# SCH_placa_Rorgerio_IGBT_2026-07-28.net
KiCad netlist of a schematic drawn in EasyEDA
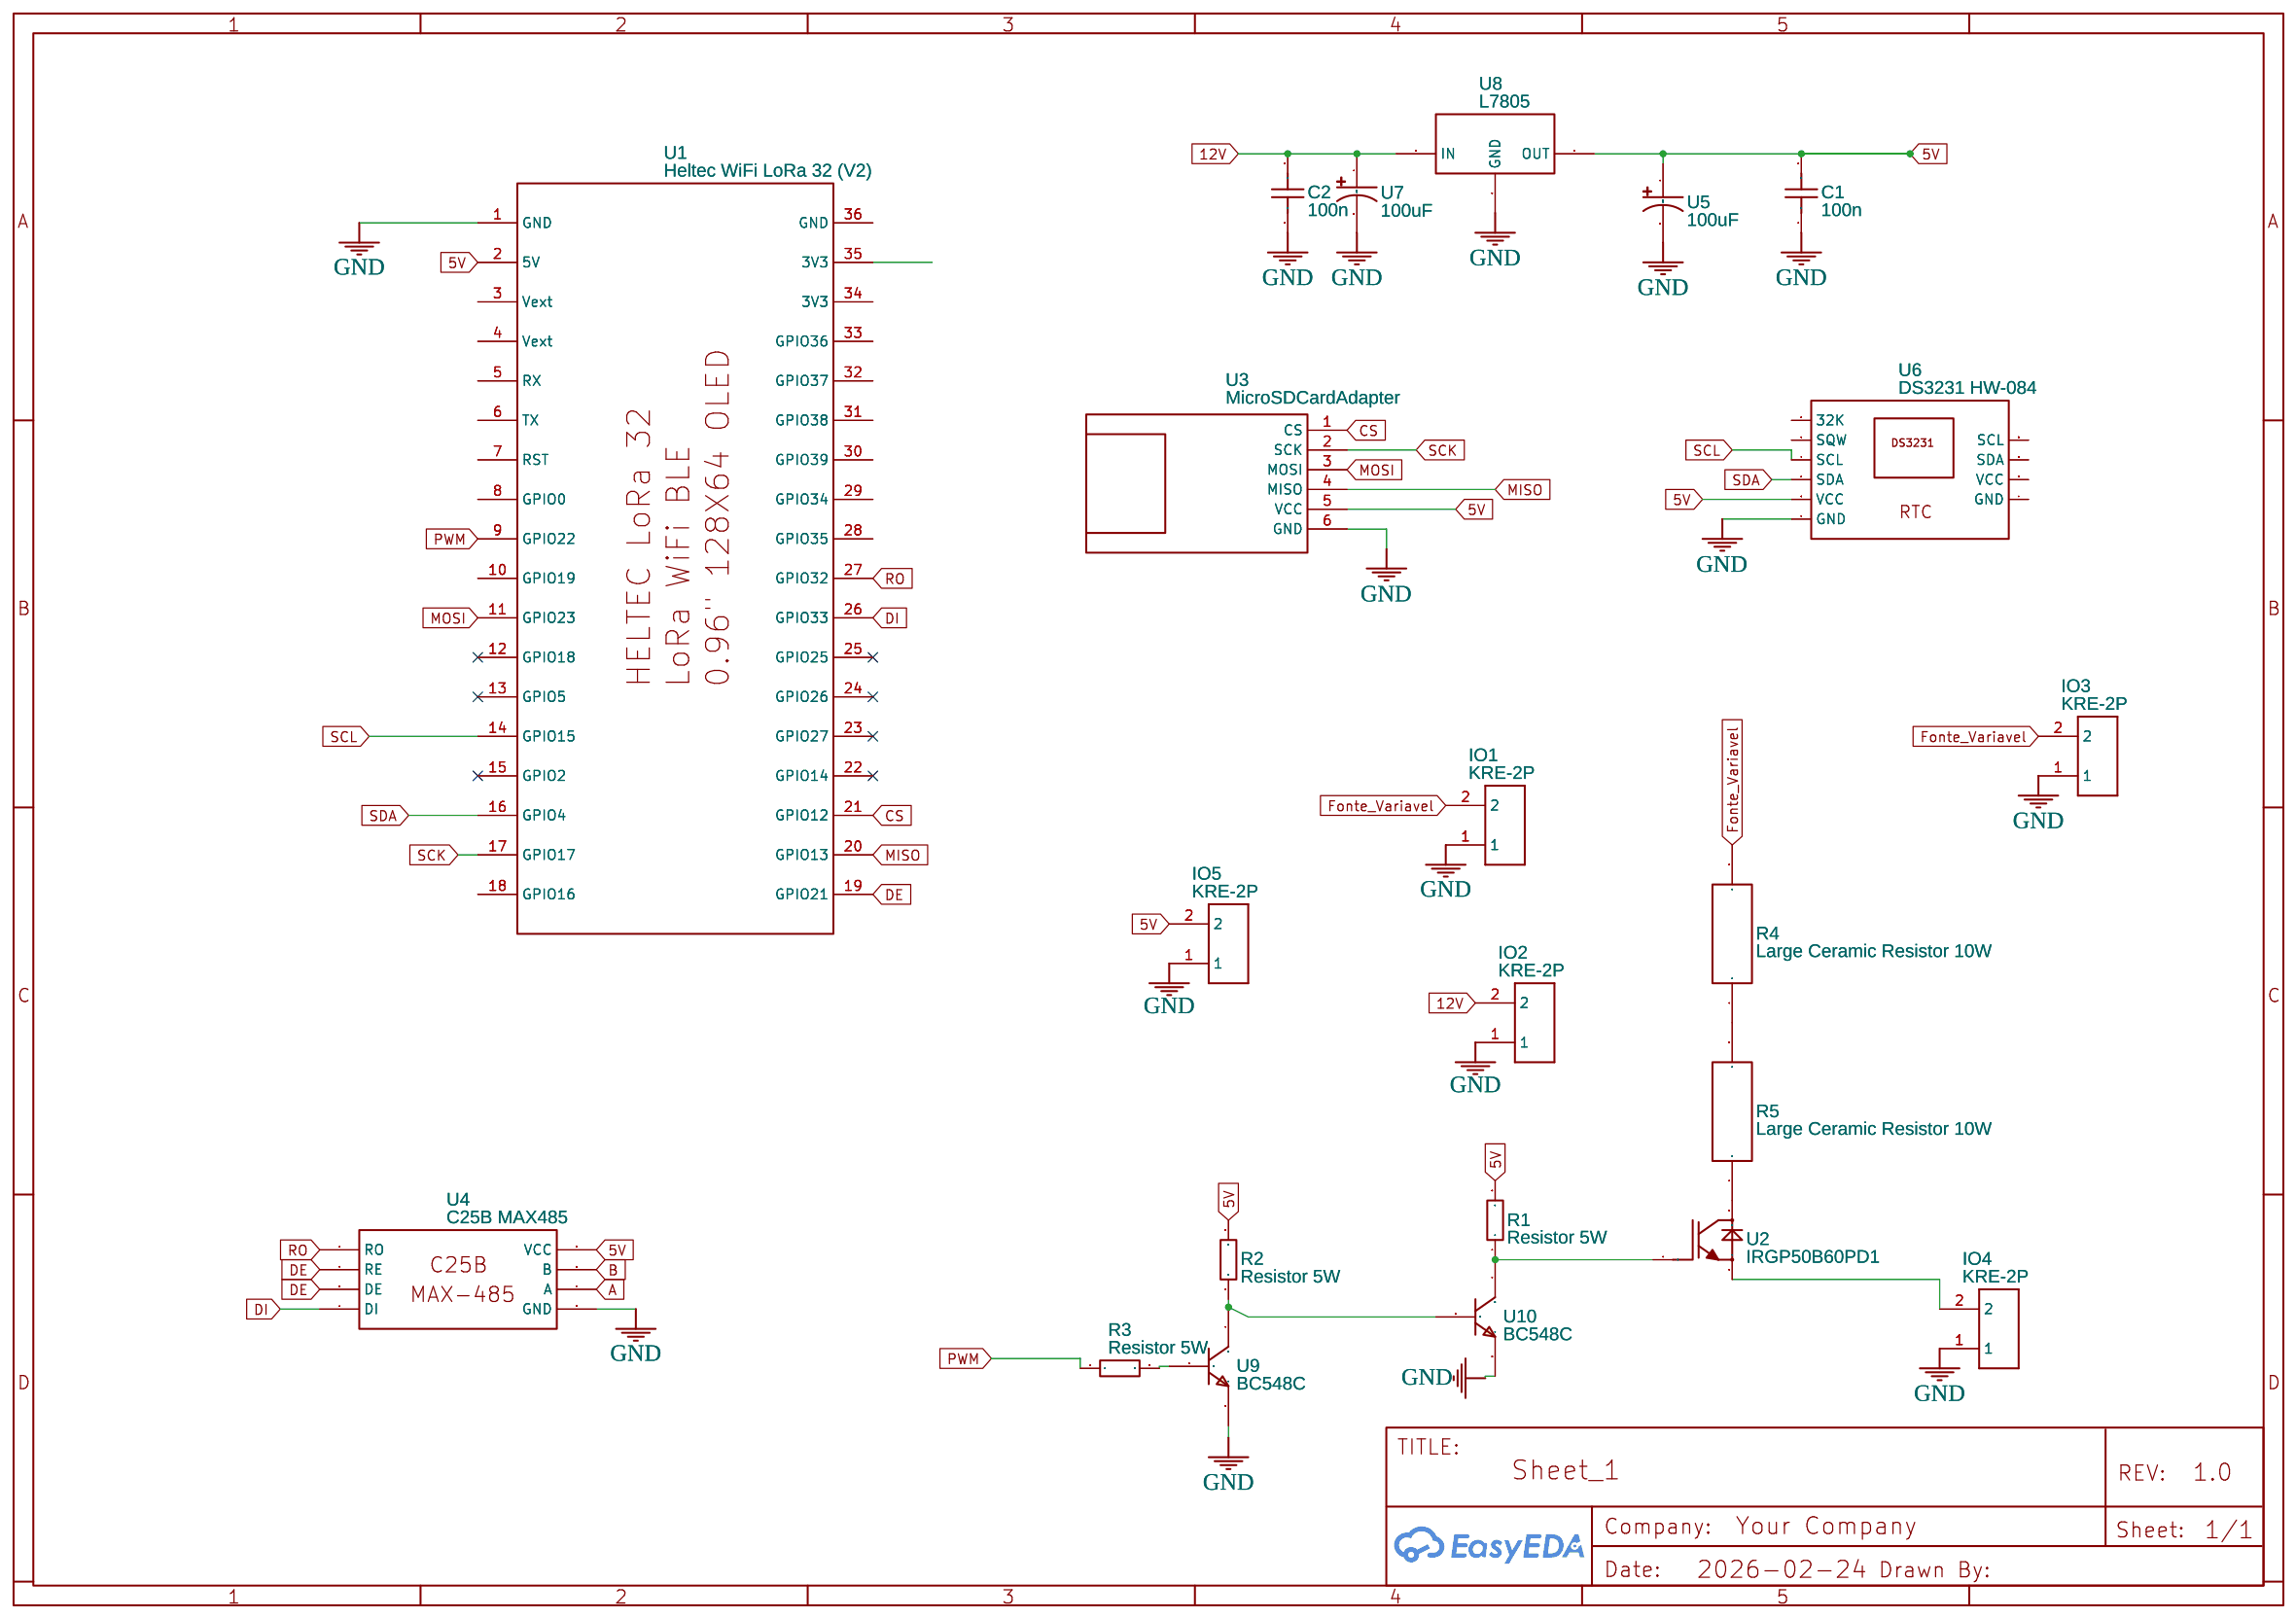
[diagram p0: schematic sheet]

(export (version "E")
  (design (tool "Eeschema 10.0.6"))
  (components
    (comp (ref "C1") (value "100n") (libsource (lib "") (part "C_0603_US")))
    (comp (ref "C2") (value "100n") (libsource (lib "") (part "C_0603_US")))
    (comp (ref "IO1") (value "KRE-2P") (libsource (lib "") (part "KRE-2P")))
    (comp (ref "IO2") (value "KRE-2P") (libsource (lib "") (part "KRE-2P")))
    (comp (ref "IO3") (value "KRE-2P") (libsource (lib "") (part "KRE-2P")))
    (comp (ref "IO4") (value "KRE-2P") (libsource (lib "") (part "KRE-2P")))
    (comp (ref "IO5") (value "KRE-2P") (libsource (lib "") (part "KRE-2P")))
    (comp (ref "R1")
      (value "Resistor 5W")
      (fields (field (name "Manufacturer") "UniOhm"))
      (libsource (lib "") (part "Resistor 5W"))
    )
    (comp (ref "R2")
      (value "Resistor 5W")
      (fields (field (name "Manufacturer") "UniOhm"))
      (libsource (lib "") (part "Resistor 5W"))
    )
    (comp (ref "R3")
      (value "Resistor 5W")
      (fields (field (name "Manufacturer") "UniOhm"))
      (libsource (lib "") (part "Resistor 5W_1"))
    )
    (comp (ref "R4")
      (value "Large Ceramic Resistor 10W")
      (fields (field (name "Manufacturer Part") "Yontex MKP 250V 6.8uF"))
      (libsource (lib "") (part "Large Ceramic Resistor 10W"))
    )
    (comp (ref "R5")
      (value "Large Ceramic Resistor 10W")
      (fields (field (name "Manufacturer Part") "Yontex MKP 250V 6.8uF"))
      (libsource (lib "") (part "Large Ceramic Resistor 10W"))
    )
    (comp (ref "U1")
      (value "Heltec WiFi LoRa 32 (V2)")
      (fields
        (field (name "Manufacturer Part") "Heltec WiFi LoRa 32(V2)")
        (field (name "Manufacturer") "Heltec")
      )
      (libsource (lib "") (part "Heltec WiFi LoRa 32 (V2)"))
    )
    (comp (ref "U2") (value "IRGP50B60PD1") (libsource (lib "") (part "IRGP50B60PD1")))
    (comp (ref "U3") (value "MicroSDCardAdapter") (libsource (lib "") (part "MicroSDCardAdapter")))
    (comp (ref "U4") (value "C25B MAX485") (libsource (lib "") (part "C25B MAX485")))
    (comp (ref "U5")
      (value "100uF")
      (fields
        (field (name "Manufacturer Part") "EKY-101ETD101MK16S")
        (field (name "Manufacturer") "NCC(日本贵弥功)")
      )
      (libsource (lib "") (part "Cap100uF25V"))
    )
    (comp (ref "U6") (value "DS3231 HW-084") (libsource (lib "") (part "DS3231 HW-084")))
    (comp (ref "U7")
      (value "100uF")
      (fields
        (field (name "Manufacturer Part") "EKY-101ETD101MK16S")
        (field (name "Manufacturer") "NCC(日本贵弥功)")
      )
      (libsource (lib "") (part "Cap100uF25V"))
    )
    (comp (ref "U8") (value "L7805") (libsource (lib "") (part "L7805")))
    (comp (ref "U9") (value "BC548C") (libsource (lib "") (part "BC548C")))
    (comp (ref "U10") (value "BC548C") (libsource (lib "") (part "BC548C")))
  )
  (nets
    (net (code "1") (name "5V") (class "Default")
      (node (ref "C1") (pin "2") (pinfunction "2_2") (pintype "unspecified"))
      (node (ref "IO5") (pin "2") (pinfunction "2_2") (pintype "unspecified"))
      (node (ref "R1") (pin "2") (pinfunction "2_2") (pintype "input"))
      (node (ref "R2") (pin "2") (pinfunction "2_2") (pintype "input"))
      (node (ref "U1") (pin "2") (pinfunction "5V_2") (pintype "unspecified"))
      (node (ref "U3") (pin "5") (pinfunction "VCC_5") (pintype "unspecified"))
      (node (ref "U4") (pin "5") (pinfunction "VCC_5") (pintype "unspecified"))
      (node (ref "U5") (pin "1") (pinfunction "1_1") (pintype "unspecified"))
      (node (ref "U6") (pin "2") (pinfunction "VCC_2") (pintype "passive"))
      (node (ref "U8") (pin "1") (pinfunction "OUT_1") (pintype "unspecified"))
    )
    (net (code "2") (name "12V") (class "Default")
      (node (ref "C2") (pin "2") (pinfunction "2_2") (pintype "unspecified"))
      (node (ref "IO2") (pin "2") (pinfunction "2_2") (pintype "unspecified"))
      (node (ref "U7") (pin "1") (pinfunction "1_1") (pintype "unspecified"))
      (node (ref "U8") (pin "3") (pinfunction "IN_3") (pintype "unspecified"))
    )
    (net (code "3") (name "A") (class "Default")
      (node (ref "U4") (pin "7") (pinfunction "A_7") (pintype "unspecified"))
    )
    (net (code "4") (name "B") (class "Default")
      (node (ref "U4") (pin "6") (pinfunction "B_6") (pintype "unspecified"))
    )
    (net (code "5") (name "CS") (class "Default")
      (node (ref "U1") (pin "21") (pinfunction "GPIO12_21") (pintype "unspecified"))
      (node (ref "U3") (pin "1") (pinfunction "CS_1") (pintype "unspecified"))
    )
    (net (code "6") (name "DE") (class "Default")
      (node (ref "U1") (pin "19") (pinfunction "GPIO21_19") (pintype "unspecified"))
      (node (ref "U4") (pin "2") (pinfunction "RE_2") (pintype "unspecified"))
      (node (ref "U4") (pin "3") (pinfunction "DE_3") (pintype "unspecified"))
    )
    (net (code "7") (name "DI") (class "Default")
      (node (ref "U1") (pin "26") (pinfunction "GPIO33_26") (pintype "unspecified"))
      (node (ref "U4") (pin "4") (pinfunction "DI_4") (pintype "unspecified"))
    )
    (net (code "8") (name "Fonte_Variavel") (class "Default")
      (node (ref "IO1") (pin "2") (pinfunction "2_2") (pintype "unspecified"))
      (node (ref "IO3") (pin "2") (pinfunction "2_2") (pintype "unspecified"))
      (node (ref "R4") (pin "2") (pinfunction "2_2") (pintype "unspecified"))
    )
    (net (code "9") (name "GND") (class "Default")
      (node (ref "C1") (pin "1") (pinfunction "1_1") (pintype "unspecified"))
      (node (ref "C2") (pin "1") (pinfunction "1_1") (pintype "unspecified"))
      (node (ref "IO1") (pin "1") (pinfunction "1_1") (pintype "unspecified"))
      (node (ref "IO2") (pin "1") (pinfunction "1_1") (pintype "unspecified"))
      (node (ref "IO3") (pin "1") (pinfunction "1_1") (pintype "unspecified"))
      (node (ref "IO4") (pin "1") (pinfunction "1_1") (pintype "unspecified"))
      (node (ref "IO5") (pin "1") (pinfunction "1_1") (pintype "unspecified"))
      (node (ref "U1") (pin "1") (pinfunction "GND_1") (pintype "unspecified"))
      (node (ref "U10") (pin "3") (pinfunction "E_3") (pintype "unspecified"))
      (node (ref "U3") (pin "6") (pinfunction "GND_6") (pintype "unspecified"))
      (node (ref "U4") (pin "8") (pinfunction "GND_8") (pintype "unspecified"))
      (node (ref "U5") (pin "2") (pinfunction "2_2") (pintype "unspecified"))
      (node (ref "U6") (pin "1") (pinfunction "GND_1") (pintype "passive"))
      (node (ref "U7") (pin "2") (pinfunction "2_2") (pintype "unspecified"))
      (node (ref "U8") (pin "2") (pinfunction "GND_2") (pintype "unspecified"))
      (node (ref "U9") (pin "3") (pinfunction "E_3") (pintype "unspecified"))
    )
    (net (code "10") (name "MISO") (class "Default")
      (node (ref "U1") (pin "20") (pinfunction "GPIO13_20") (pintype "unspecified"))
      (node (ref "U3") (pin "4") (pinfunction "MISO_4") (pintype "unspecified"))
    )
    (net (code "11") (name "MOSI") (class "Default")
      (node (ref "U1") (pin "11") (pinfunction "GPIO23_11") (pintype "unspecified"))
      (node (ref "U3") (pin "3") (pinfunction "MOSI_3") (pintype "unspecified"))
    )
    (net (code "12") (name "Net-(R4-Pad1)") (class "Default")
      (node (ref "R4") (pin "1") (pinfunction "1_1") (pintype "unspecified"))
      (node (ref "R5") (pin "2") (pinfunction "2_2") (pintype "unspecified"))
    )
    (net (code "13") (name "Net-(U2-C)") (class "Default")
      (node (ref "R5") (pin "1") (pinfunction "1_1") (pintype "unspecified"))
      (node (ref "U2") (pin "2") (pinfunction "C_2") (pintype "unspecified"))
    )
    (net (code "14") (name "Net-(U2-E)") (class "Default")
      (node (ref "IO4") (pin "2") (pinfunction "2_2") (pintype "unspecified"))
      (node (ref "U2") (pin "3") (pinfunction "E_3") (pintype "unspecified"))
    )
    (net (code "15") (name "Net-(U9-B)") (class "Default")
      (node (ref "R3") (pin "2") (pinfunction "2_2") (pintype "input"))
      (node (ref "U9") (pin "2") (pinfunction "B_2") (pintype "unspecified"))
    )
    (net (code "16") (name "Net-(U10-B)") (class "Default")
      (node (ref "R2") (pin "1") (pinfunction "1_1") (pintype "input"))
      (node (ref "U10") (pin "2") (pinfunction "B_2") (pintype "unspecified"))
      (node (ref "U9") (pin "1") (pinfunction "C_1") (pintype "unspecified"))
    )
    (net (code "17") (name "Net-(U10-C)") (class "Default")
      (node (ref "R1") (pin "1") (pinfunction "1_1") (pintype "input"))
      (node (ref "U10") (pin "1") (pinfunction "C_1") (pintype "unspecified"))
      (node (ref "U2") (pin "1") (pinfunction "G_1") (pintype "unspecified"))
    )
    (net (code "18") (name "PWM") (class "Default")
      (node (ref "R3") (pin "1") (pinfunction "1_1") (pintype "input"))
      (node (ref "U1") (pin "9") (pinfunction "GPIO22_9") (pintype "unspecified"))
    )
    (net (code "19") (name "RO") (class "Default")
      (node (ref "U1") (pin "27") (pinfunction "GPIO32_27") (pintype "unspecified"))
      (node (ref "U4") (pin "1") (pinfunction "RO_1") (pintype "unspecified"))
    )
    (net (code "20") (name "SCK") (class "Default")
      (node (ref "U1") (pin "17") (pinfunction "GPIO17_17") (pintype "unspecified"))
      (node (ref "U3") (pin "2") (pinfunction "SCK_2") (pintype "unspecified"))
    )
    (net (code "21") (name "SCL") (class "Default")
      (node (ref "U1") (pin "14") (pinfunction "GPIO15_14") (pintype "unspecified"))
      (node (ref "U6") (pin "4") (pinfunction "SCL_4") (pintype "unspecified"))
    )
    (net (code "22") (name "SDA") (class "Default")
      (node (ref "U1") (pin "16") (pinfunction "GPIO4_16") (pintype "unspecified"))
      (node (ref "U6") (pin "3") (pinfunction "SDA_3") (pintype "bidirectional"))
    )
    (net (code "23") (name "unconnected-(U1-3V3-Pad34)") (class "Default")
      (node (ref "U1") (pin "34") (pinfunction "3V3_34") (pintype "unspecified"))
    )
    (net (code "24") (name "unconnected-(U1-3V3-Pad35)") (class "Default")
      (node (ref "U1") (pin "35") (pinfunction "3V3_35") (pintype "unspecified"))
    )
    (net (code "25") (name "unconnected-(U1-GND-Pad36)") (class "Default")
      (node (ref "U1") (pin "36") (pinfunction "GND_36") (pintype "unspecified"))
    )
    (net (code "26") (name "unconnected-(U1-GPIO0-Pad8)") (class "Default")
      (node (ref "U1") (pin "8") (pinfunction "GPIO0_8") (pintype "unspecified"))
    )
    (net (code "27") (name "unconnected-(U1-GPIO2-Pad15)") (class "Default")
      (node (ref "U1") (pin "15") (pinfunction "GPIO2_15") (pintype "unspecified+no_connect"))
    )
    (net (code "28") (name "unconnected-(U1-GPIO5-Pad13)") (class "Default")
      (node (ref "U1") (pin "13") (pinfunction "GPIO5_13") (pintype "unspecified+no_connect"))
    )
    (net (code "29") (name "unconnected-(U1-GPIO14-Pad22)") (class "Default")
      (node (ref "U1") (pin "22") (pinfunction "GPIO14_22") (pintype "unspecified+no_connect"))
    )
    (net (code "30") (name "unconnected-(U1-GPIO16-Pad18)") (class "Default")
      (node (ref "U1") (pin "18") (pinfunction "GPIO16_18") (pintype "unspecified"))
    )
    (net (code "31") (name "unconnected-(U1-GPIO18-Pad12)") (class "Default")
      (node (ref "U1") (pin "12") (pinfunction "GPIO18_12") (pintype "unspecified+no_connect"))
    )
    (net (code "32") (name "unconnected-(U1-GPIO19-Pad10)") (class "Default")
      (node (ref "U1") (pin "10") (pinfunction "GPIO19_10") (pintype "unspecified"))
    )
    (net (code "33") (name "unconnected-(U1-GPIO25-Pad25)") (class "Default")
      (node (ref "U1") (pin "25") (pinfunction "GPIO25_25") (pintype "unspecified+no_connect"))
    )
    (net (code "34") (name "unconnected-(U1-GPIO26-Pad24)") (class "Default")
      (node (ref "U1") (pin "24") (pinfunction "GPIO26_24") (pintype "unspecified+no_connect"))
    )
    (net (code "35") (name "unconnected-(U1-GPIO27-Pad23)") (class "Default")
      (node (ref "U1") (pin "23") (pinfunction "GPIO27_23") (pintype "unspecified+no_connect"))
    )
    (net (code "36") (name "unconnected-(U1-GPIO34-Pad29)") (class "Default")
      (node (ref "U1") (pin "29") (pinfunction "GPIO34_29") (pintype "unspecified"))
    )
    (net (code "37") (name "unconnected-(U1-GPIO35-Pad28)") (class "Default")
      (node (ref "U1") (pin "28") (pinfunction "GPIO35_28") (pintype "unspecified"))
    )
    (net (code "38") (name "unconnected-(U1-GPIO36-Pad33)") (class "Default")
      (node (ref "U1") (pin "33") (pinfunction "GPIO36_33") (pintype "unspecified"))
    )
    (net (code "39") (name "unconnected-(U1-GPIO37-Pad32)") (class "Default")
      (node (ref "U1") (pin "32") (pinfunction "GPIO37_32") (pintype "unspecified"))
    )
    (net (code "40") (name "unconnected-(U1-GPIO38-Pad31)") (class "Default")
      (node (ref "U1") (pin "31") (pinfunction "GPIO38_31") (pintype "unspecified"))
    )
    (net (code "41") (name "unconnected-(U1-GPIO39-Pad30)") (class "Default")
      (node (ref "U1") (pin "30") (pinfunction "GPIO39_30") (pintype "unspecified"))
    )
    (net (code "42") (name "unconnected-(U1-RST-Pad7)") (class "Default")
      (node (ref "U1") (pin "7") (pinfunction "RST_7") (pintype "unspecified"))
    )
    (net (code "43") (name "unconnected-(U1-RX-Pad5)") (class "Default")
      (node (ref "U1") (pin "5") (pinfunction "RX_5") (pintype "unspecified"))
    )
    (net (code "44") (name "unconnected-(U1-TX-Pad6)") (class "Default")
      (node (ref "U1") (pin "6") (pinfunction "TX_6") (pintype "unspecified"))
    )
    (net (code "45") (name "unconnected-(U1-Vext-Pad3)") (class "Default")
      (node (ref "U1") (pin "3") (pinfunction "Vext_3") (pintype "unspecified"))
    )
    (net (code "46") (name "unconnected-(U1-Vext-Pad4)") (class "Default")
      (node (ref "U1") (pin "4") (pinfunction "Vext_4") (pintype "unspecified"))
    )
    (net (code "47") (name "unconnected-(U6-32K-Pad6)") (class "Default")
      (node (ref "U6") (pin "6") (pinfunction "32K_6") (pintype "input"))
    )
    (net (code "48") (name "unconnected-(U6-GND-Pad7)") (class "Default")
      (node (ref "U6") (pin "7") (pinfunction "GND_7") (pintype "passive"))
    )
    (net (code "49") (name "unconnected-(U6-SCL-Pad10)") (class "Default")
      (node (ref "U6") (pin "10") (pinfunction "SCL_10") (pintype "unspecified"))
    )
    (net (code "50") (name "unconnected-(U6-SDA-Pad9)") (class "Default")
      (node (ref "U6") (pin "9") (pinfunction "SDA_9") (pintype "bidirectional"))
    )
    (net (code "51") (name "unconnected-(U6-SQW-Pad5)") (class "Default")
      (node (ref "U6") (pin "5") (pinfunction "SQW_5") (pintype "input"))
    )
    (net (code "52") (name "unconnected-(U6-VCC-Pad8)") (class "Default")
      (node (ref "U6") (pin "8") (pinfunction "VCC_8") (pintype "passive"))
    )
  )
)
